# Suiveur.net
KiCad netlist of a schematic drawn in Altium Designer
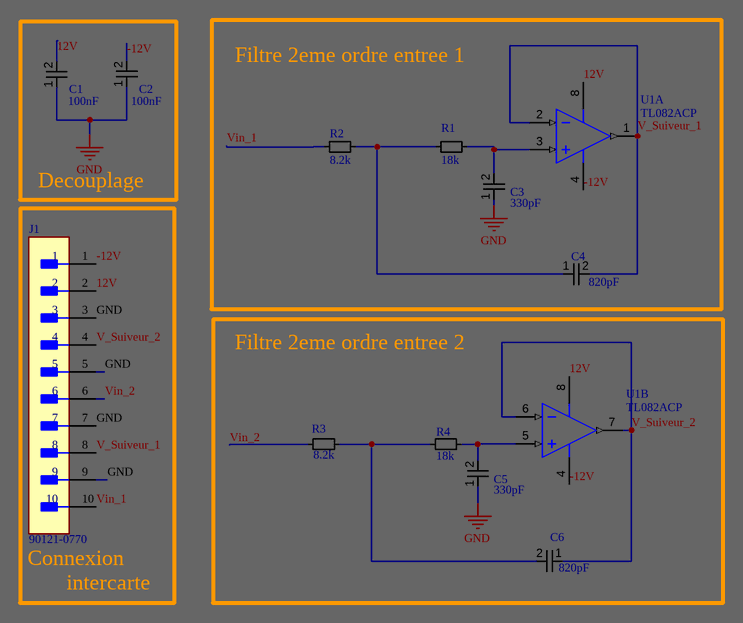
[diagram p0: Suiveur.SchDoc]

(export (version "E")
  (design (tool "Eeschema 10.0.6"))
  (components
    (comp (ref "C1")
      (value "100nF")
      (footprint "PCB:Cap_6.0%2A2.5%2A6mm")
      (fields (field (name "Comment") "Cap_6.0*2.5*6mm"))
      (libsource (lib "Schema") (part "Cap_6.0*2.5*6mm"))
    )
    (comp (ref "C2")
      (value "100nF")
      (footprint "PCB:Cap_6.0%2A2.5%2A6mm")
      (fields (field (name "Comment") "Cap_6.0*2.5*6mm"))
      (libsource (lib "Schema") (part "Cap_6.0*2.5*6mm"))
    )
    (comp (ref "C3")
      (value "330pF")
      (footprint "PCB:Cap_6.0%2A2.5%2A6mm")
      (fields (field (name "Comment") "Cap_6.0*2.5*6mm"))
      (libsource (lib "Schema") (part "Cap_6.0*2.5*6mm"))
    )
    (comp (ref "C4")
      (value "820pF")
      (footprint "PCB:Cap_6.0%2A2.5%2A6mm")
      (fields (field (name "Comment") "Cap_6.0*2.5*6mm"))
      (libsource (lib "Schema") (part "Cap_6.0*2.5*6mm"))
    )
    (comp (ref "C5")
      (value "330pF")
      (footprint "PCB:Cap_6.0%2A2.5%2A6mm")
      (fields (field (name "Comment") "Cap_6.0*2.5*6mm"))
      (libsource (lib "Schema") (part "Cap_6.0*2.5*6mm"))
    )
    (comp (ref "C6")
      (value "820pF")
      (footprint "PCB:Cap_6.0%2A2.5%2A6mm")
      (fields (field (name "Comment") "Cap_6.0*2.5*6mm"))
      (libsource (lib "Schema") (part "Cap_6.0*2.5*6mm"))
    )
    (comp (ref "J1")
      (value "90121-0770")
      (footprint "FP-90121-0770-MFG")
      (description "CONN HEADER R/A 10POS 2.54MM")
      (libsource (lib "Altium Content Vault") (part "aee40dc8b284c03a16094555aa210be"))
    )
    (comp (ref "R1")
      (value "18k")
      (footprint "PCB:Res_Axial_3.5x6.5mm_TH")
      (fields (field (name "Comment") "Res_3.5x6.5mm_TH"))
      (libsource (lib "Schema") (part "Res_3.5x6.5mm_TH"))
    )
    (comp (ref "R2")
      (value "8.2k")
      (footprint "PCB:Res_Axial_3.5x6.5mm_TH")
      (fields (field (name "Comment") "Res_3.5x6.5mm_TH"))
      (libsource (lib "Schema") (part "Res_3.5x6.5mm_TH"))
    )
    (comp (ref "R3")
      (value "8.2k")
      (footprint "PCB:Res_Axial_3.5x6.5mm_TH")
      (fields (field (name "Comment") "Res_3.5x6.5mm_TH"))
      (libsource (lib "Schema") (part "Res_3.5x6.5mm_TH"))
    )
    (comp (ref "R4")
      (value "18k")
      (footprint "PCB:Res_Axial_3.5x6.5mm_TH")
      (fields (field (name "Comment") "Res_3.5x6.5mm_TH"))
      (libsource (lib "Schema") (part "Res_3.5x6.5mm_TH"))
    )
    (comp (ref "U1")
      (value "TL082ACP")
      (footprint "P0008A")
      (description "JFET-Input Operational Amplifier, 7 to 36 V, 0 to 70 degC, 8-pin DIP (P8), Pb-Free (RoHS)")
      (fields (field (name "MANUFACTURER") "Texas Instruments"))
      (libsource (lib "Altium Content Vault") (part "TI-AMP-D6-2-8_D"))
    )
  )
  (nets
    (net (code "1") (name "/-12V") (class "Default")
      (node (ref "C2") (pin "2") (pinfunction "2_2") (pintype "passive"))
      (node (ref "J1") (pin "1") (pinfunction "1_1") (pintype "passive"))
      (node (ref "U1") (pin "4") (pinfunction "VCC-_4") (pintype "power_in"))
    )
    (net (code "2") (name "/12V") (class "Default")
      (node (ref "C1") (pin "2") (pinfunction "2_2") (pintype "passive"))
      (node (ref "J1") (pin "2") (pinfunction "2_2") (pintype "passive"))
      (node (ref "U1") (pin "8") (pinfunction "VCC+_8") (pintype "power_in"))
    )
    (net (code "3") (name "/V_Suiveur_1") (class "Default")
      (node (ref "C4") (pin "2") (pinfunction "2_2") (pintype "passive"))
      (node (ref "J1") (pin "8") (pinfunction "8_8") (pintype "passive"))
      (node (ref "U1") (pin "1") (pinfunction "OUT1_1") (pintype "output"))
      (node (ref "U1") (pin "2") (pinfunction "IN1-_2") (pintype "input"))
    )
    (net (code "4") (name "/V_Suiveur_2") (class "Default")
      (node (ref "C6") (pin "1") (pinfunction "1_1") (pintype "passive"))
      (node (ref "J1") (pin "4") (pinfunction "4_4") (pintype "passive"))
      (node (ref "U1") (pin "6") (pinfunction "IN2-_6") (pintype "input"))
      (node (ref "U1") (pin "7") (pinfunction "OUT2_7") (pintype "output"))
    )
    (net (code "5") (name "/Vin_1") (class "Default")
      (node (ref "J1") (pin "10") (pinfunction "10_10") (pintype "passive"))
      (node (ref "R2") (pin "0") (pintype "passive"))
    )
    (net (code "6") (name "/Vin_2") (class "Default")
      (node (ref "J1") (pin "6") (pinfunction "6_6") (pintype "passive"))
      (node (ref "R3") (pin "0") (pintype "passive"))
    )
    (net (code "7") (name "GND") (class "Default")
      (node (ref "C1") (pin "1") (pinfunction "1_1") (pintype "passive"))
      (node (ref "C2") (pin "1") (pinfunction "1_1") (pintype "passive"))
      (node (ref "C3") (pin "1") (pinfunction "1_1") (pintype "passive"))
      (node (ref "C5") (pin "1") (pinfunction "1_1") (pintype "passive"))
      (node (ref "J1") (pin "3") (pinfunction "3_3") (pintype "passive"))
      (node (ref "J1") (pin "5") (pinfunction "5_5") (pintype "passive"))
      (node (ref "J1") (pin "7") (pinfunction "7_7") (pintype "passive"))
      (node (ref "J1") (pin "9") (pinfunction "9_9") (pintype "passive"))
    )
    (net (code "8") (name "Net-(C4-Pad1)") (class "Default")
      (node (ref "C4") (pin "1") (pinfunction "1_1") (pintype "passive"))
      (node (ref "R1") (pin "0") (pintype "passive"))
      (node (ref "R2") (pin "1") (pintype "passive"))
    )
    (net (code "9") (name "Net-(C6-Pad2)") (class "Default")
      (node (ref "C6") (pin "2") (pinfunction "2_2") (pintype "passive"))
      (node (ref "R3") (pin "1") (pintype "passive"))
      (node (ref "R4") (pin "0") (pintype "passive"))
    )
    (net (code "10") (name "Net-(U1A-IN1+)") (class "Default")
      (node (ref "C3") (pin "2") (pinfunction "2_2") (pintype "passive"))
      (node (ref "R1") (pin "1") (pintype "passive"))
      (node (ref "U1") (pin "3") (pinfunction "IN1+_3") (pintype "input"))
    )
    (net (code "11") (name "Net-(U1B-IN2+)") (class "Default")
      (node (ref "C5") (pin "2") (pinfunction "2_2") (pintype "passive"))
      (node (ref "R4") (pin "1") (pintype "passive"))
      (node (ref "U1") (pin "5") (pinfunction "IN2+_5") (pintype "input"))
    )
  )
)
